# RadioGateway.net
KiCad netlist of a schematic drawn in EAGLE
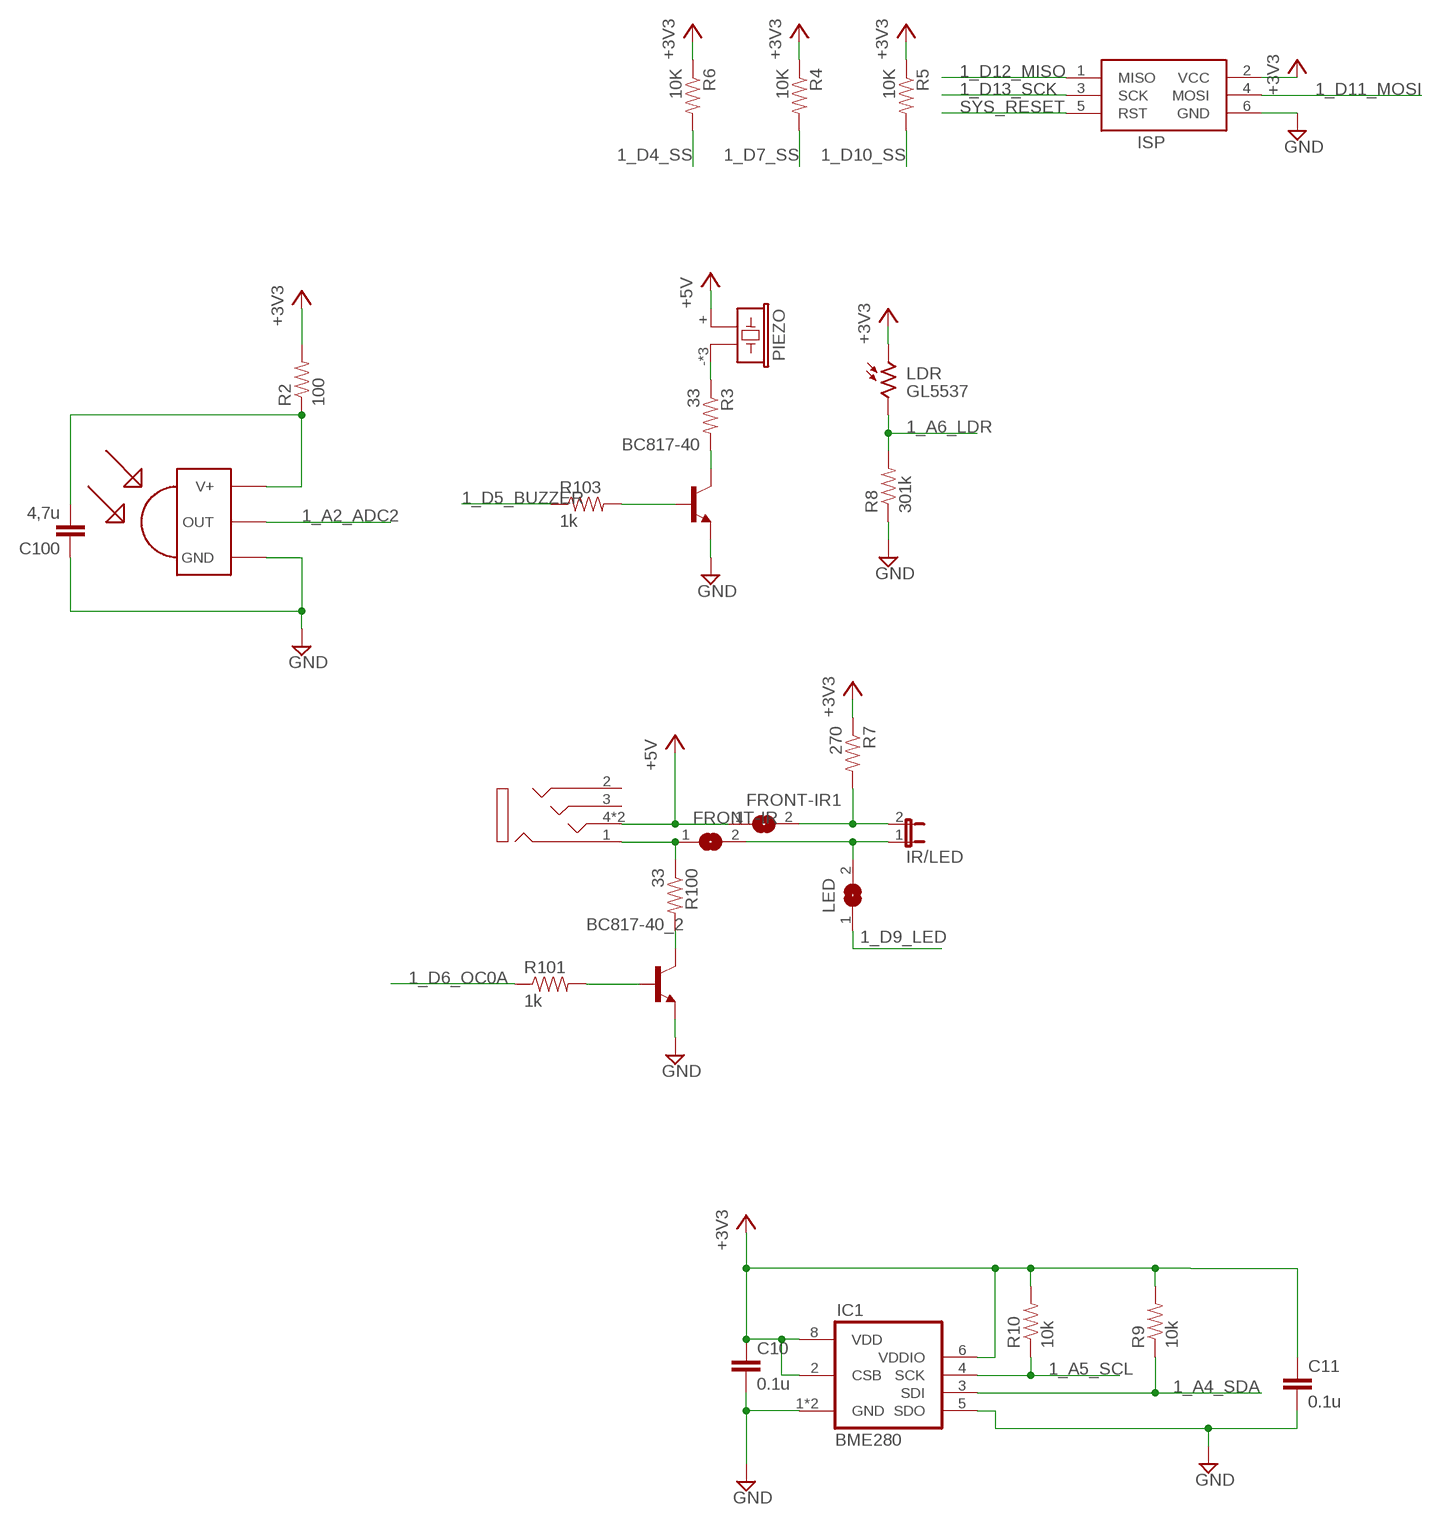
[diagram p0: schematic, sheet 1, part 1 of 2]
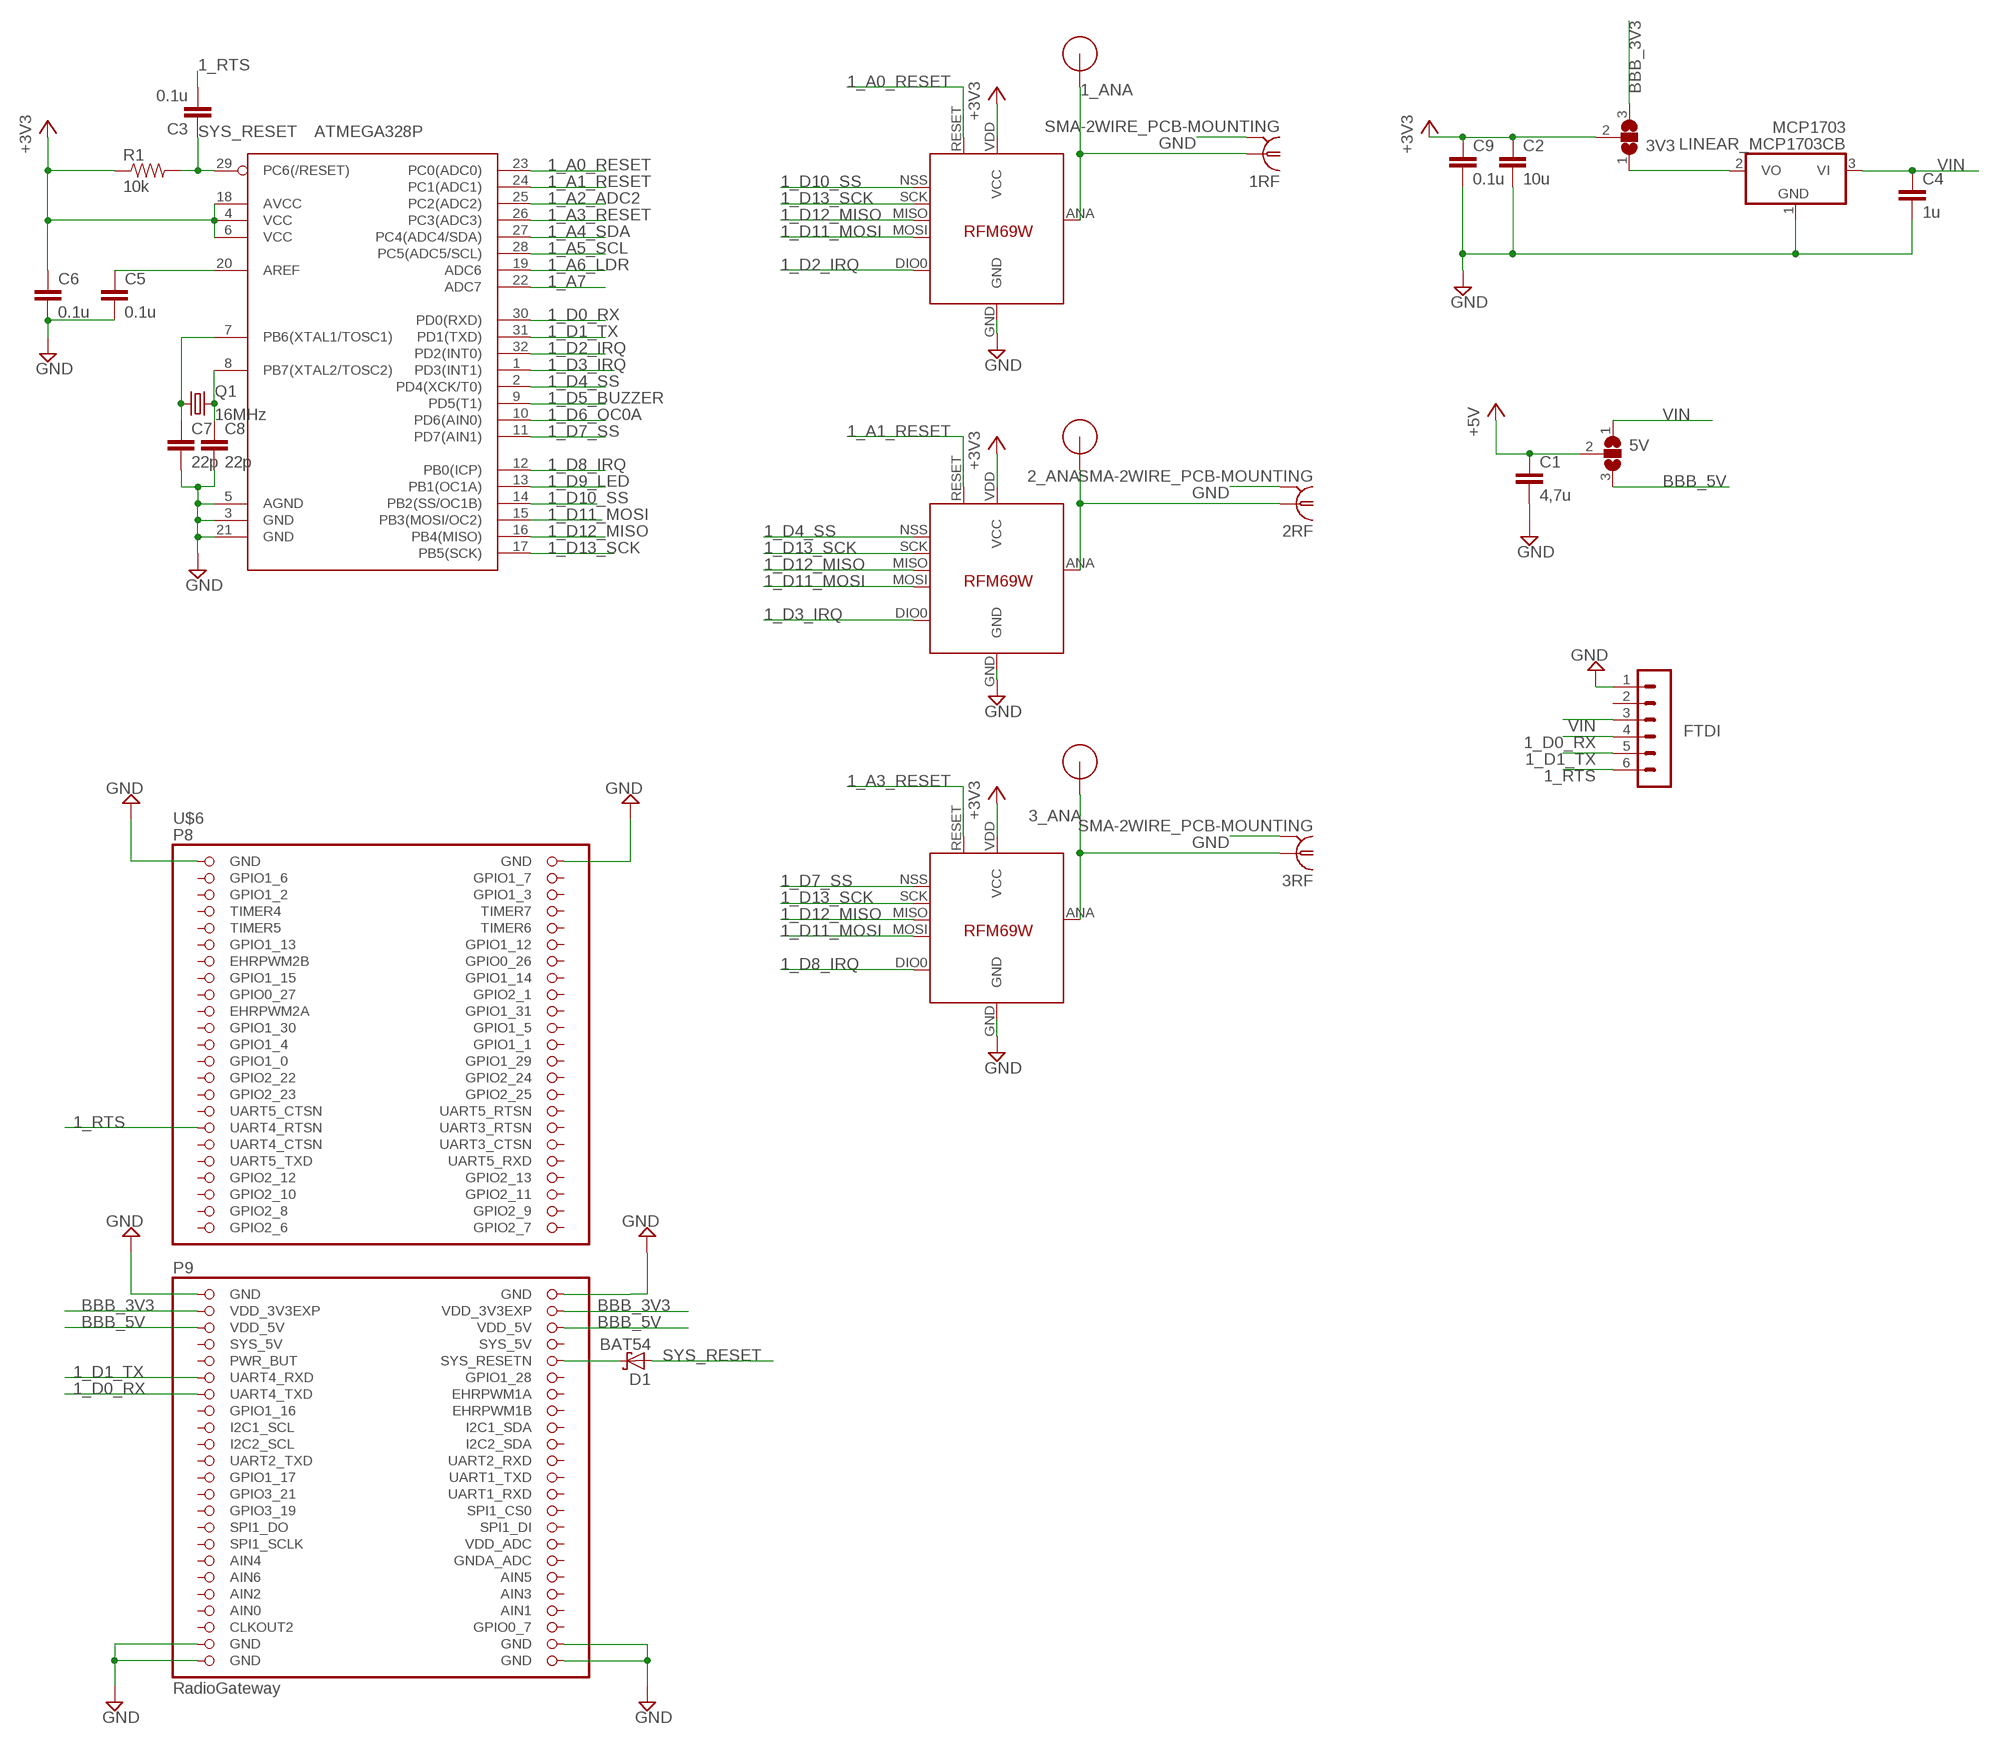
[diagram p1: schematic, sheet 1, part 2 of 2]

(export (version "E")
  (design (tool "Eeschema 10.0.6"))
  (components
    (comp (ref "1RF")
      (value "SMA-2WIRE_PCB-MOUNTING")
      (footprint "eagle-import:J01151A0931")
      (libsource (lib "eagle-import") (part "SMA-2WIRE_PCB-MOUNTING"))
    )
    (comp (ref "1_RFM69")
      (value "RFM69_MINIPADS")
      (footprint "eagle-import:RFM69W-MINPADS")
      (libsource (lib "eagle-import") (part "RFM69_MINIPADS"))
    )
    (comp (ref "2RF")
      (value "SMA-2WIRE_PCB-MOUNTING")
      (footprint "eagle-import:J01151A0931")
      (libsource (lib "eagle-import") (part "SMA-2WIRE_PCB-MOUNTING"))
    )
    (comp (ref "2_RFM69")
      (value "RFM69_MINIPADS")
      (footprint "eagle-import:RFM69W-MINPADS")
      (libsource (lib "eagle-import") (part "RFM69_MINIPADS"))
    )
    (comp (ref "3RF")
      (value "SMA-2WIRE_PCB-MOUNTING")
      (footprint "eagle-import:J01151A0931")
      (libsource (lib "eagle-import") (part "SMA-2WIRE_PCB-MOUNTING"))
    )
    (comp (ref "3V3")
      (value "SJ2W")
      (footprint "eagle-import:SJ_2")
      (libsource (lib "eagle-import") (part "SJ2W"))
    )
    (comp (ref "3_RFM69")
      (value "RFM69_MINIPADS")
      (footprint "eagle-import:RFM69W-MINPADS")
      (libsource (lib "eagle-import") (part "RFM69_MINIPADS"))
    )
    (comp (ref "5V")
      (value "SJ2W")
      (footprint "eagle-import:SJ_2")
      (libsource (lib "eagle-import") (part "SJ2W"))
    )
    (comp (ref "ATMEGA328P")
      (value "ATMega-328")
      (footprint "eagle-import:TQFP32-08")
      (libsource (lib "eagle-import") (part "ATMEGA168/328TQFP32"))
    )
    (comp (ref "BC817-40")
      (value "BC817-40-NPN-SOT23-BEC")
      (footprint "eagle-import:SOT23-BEC")
      (libsource (lib "eagle-import") (part "-NPN-SOT23-BECBC817-40"))
    )
    (comp (ref "BC817-40_2")
      (value "BC817-40-NPN-SOT23-BEC")
      (footprint "eagle-import:SOT23-BEC")
      (libsource (lib "eagle-import") (part "-NPN-SOT23-BECBC817-40"))
    )
    (comp (ref "C1")
      (value "4,7u")
      (footprint "eagle-import:0603-CAP")
      (libsource (lib "eagle-import") (part "CAP0603-CAP"))
    )
    (comp (ref "C2")
      (value "10u")
      (footprint "eagle-import:0603-CAP")
      (libsource (lib "eagle-import") (part "CAP0603-CAP"))
    )
    (comp (ref "C3")
      (value "0.1u")
      (footprint "eagle-import:0603-CAP")
      (libsource (lib "eagle-import") (part "CAP0603-CAP"))
    )
    (comp (ref "C4")
      (value "1u")
      (footprint "eagle-import:0603-CAP")
      (libsource (lib "eagle-import") (part "CAP0603-CAP"))
    )
    (comp (ref "C5")
      (value "0.1u")
      (footprint "eagle-import:0603-CAP")
      (libsource (lib "eagle-import") (part "CAP0603-CAP"))
    )
    (comp (ref "C6")
      (value "0.1u")
      (footprint "eagle-import:0603-CAP")
      (libsource (lib "eagle-import") (part "CAP0603-CAP"))
    )
    (comp (ref "C7")
      (value "22p")
      (footprint "eagle-import:0603-CAP")
      (libsource (lib "eagle-import") (part "CAP0603-CAP"))
    )
    (comp (ref "C8")
      (value "22p")
      (footprint "eagle-import:0603-CAP")
      (libsource (lib "eagle-import") (part "CAP0603-CAP"))
    )
    (comp (ref "C9")
      (value "0.1u")
      (footprint "eagle-import:0603-CAP")
      (libsource (lib "eagle-import") (part "CAP0603-CAP"))
    )
    (comp (ref "C10")
      (value "0.1u")
      (footprint "eagle-import:0603-CAP")
      (libsource (lib "eagle-import") (part "CAP0603-CAP"))
    )
    (comp (ref "C11")
      (value "0.1u")
      (footprint "eagle-import:0603-CAP")
      (libsource (lib "eagle-import") (part "CAP0603-CAP"))
    )
    (comp (ref "C100")
      (value "4,7u")
      (footprint "eagle-import:0603-CAP")
      (libsource (lib "eagle-import") (part "CAP0603-CAP"))
    )
    (comp (ref "D1")
      (value "BAT54")
      (footprint "eagle-import:SOT23")
      (libsource (lib "eagle-import") (part "BAT54"))
    )
    (comp (ref "FRONT-IR")
      (value "SJ")
      (footprint "eagle-import:SJ")
      (libsource (lib "eagle-import") (part "SJ"))
    )
    (comp (ref "FRONT-IR1")
      (value "SJ")
      (footprint "eagle-import:SJ")
      (libsource (lib "eagle-import") (part "SJ"))
    )
    (comp (ref "FTDI")
      (value "FTDI")
      (footprint "eagle-import:MA06-1")
      (libsource (lib "eagle-import") (part "MA06-1"))
    )
    (comp (ref "IC1")
      (value "BME280")
      (footprint "eagle-import:BME280")
      (libsource (lib "eagle-import") (part "BME280"))
    )
    (comp (ref "IR-RX")
      (value "TSOP4836")
      (footprint "eagle-import:TSOP18XX")
      (libsource (lib "eagle-import") (part "TSOP4836"))
    )
    (comp (ref "IR-TX")
      (value "1503_13")
      (footprint "eagle-import:1503-03")
      (libsource (lib "eagle-import") (part "1503_13"))
    )
    (comp (ref "IR/LED")
      (value "JP1E")
      (footprint "eagle-import:JP1")
      (libsource (lib "eagle-import") (part "JP1E"))
    )
    (comp (ref "ISP")
      (value "AVRISP-6")
      (footprint "eagle-import:AVRISP")
      (libsource (lib "eagle-import") (part "AVRISP-6"))
    )
    (comp (ref "LDR")
      (value "GL5537")
      (footprint "eagle-import:M9960")
      (libsource (lib "eagle-import") (part "M9960_11A"))
    )
    (comp (ref "LED") (value "SJ") (footprint "eagle-import:SJ") (libsource (lib "eagle-import") (part "SJ")))
    (comp (ref "MCP1703")
      (value "LINEAR_MCP1703CB")
      (footprint "eagle-import:LINEAR_SOT23")
      (libsource (lib "eagle-import") (part "LINEAR_MCP1703CB"))
    )
    (comp (ref "PIEZO")
      (value "BUZZER-PIEZO_SMD")
      (footprint "eagle-import:BUZZER-PIEZO_SMD")
      (libsource (lib "eagle-import") (part "BUZZER-PIEZO_SMD"))
    )
    (comp (ref "Q1")
      (value "16MHz")
      (footprint "eagle-import:HC49_S")
      (libsource (lib "eagle-import") (part "CRYSTALHC49S"))
    )
    (comp (ref "R1")
      (value "10k")
      (footprint "eagle-import:0603-RES")
      (libsource (lib "eagle-import") (part "RESISTOR0603-RES"))
    )
    (comp (ref "R2")
      (value "100")
      (footprint "eagle-import:0603-RES")
      (libsource (lib "eagle-import") (part "RESISTOR0603-RES"))
    )
    (comp (ref "R3")
      (value "33")
      (footprint "eagle-import:0603-RES")
      (libsource (lib "eagle-import") (part "RESISTOR0603-RES"))
    )
    (comp (ref "R4")
      (value "10K")
      (footprint "eagle-import:0603-RES")
      (libsource (lib "eagle-import") (part "RESISTOR0603-RES"))
    )
    (comp (ref "R5")
      (value "10K")
      (footprint "eagle-import:0603-RES")
      (libsource (lib "eagle-import") (part "RESISTOR0603-RES"))
    )
    (comp (ref "R6")
      (value "10K")
      (footprint "eagle-import:0603-RES")
      (libsource (lib "eagle-import") (part "RESISTOR0603-RES"))
    )
    (comp (ref "R7")
      (value "270")
      (footprint "eagle-import:0603-RES")
      (libsource (lib "eagle-import") (part "RESISTOR0603-RES"))
    )
    (comp (ref "R8")
      (value "301k")
      (footprint "eagle-import:0603-RES")
      (libsource (lib "eagle-import") (part "RESISTOR0603-RES"))
    )
    (comp (ref "R9")
      (value "10k")
      (footprint "eagle-import:0603-RES")
      (libsource (lib "eagle-import") (part "RESISTOR0603-RES"))
    )
    (comp (ref "R10")
      (value "10k")
      (footprint "eagle-import:0603-RES")
      (libsource (lib "eagle-import") (part "RESISTOR0603-RES"))
    )
    (comp (ref "R100")
      (value "33")
      (footprint "eagle-import:0603-RES")
      (libsource (lib "eagle-import") (part "RESISTOR0603-RES"))
    )
    (comp (ref "R101")
      (value "1k")
      (footprint "eagle-import:0603-RES")
      (libsource (lib "eagle-import") (part "RESISTOR0603-RES"))
    )
    (comp (ref "R103")
      (value "1k")
      (footprint "eagle-import:0603-RES")
      (libsource (lib "eagle-import") (part "RESISTOR0603-RES"))
    )
    (comp (ref "U$1")
      (value "RFM12B_ANTENNA")
      (footprint "eagle-import:RFM12B-ANTENNA")
      (libsource (lib "eagle-import") (part "RFM12B_ANTENNA"))
    )
    (comp (ref "U$2")
      (value "RFM12B_ANTENNA")
      (footprint "eagle-import:RFM12B-ANTENNA")
      (libsource (lib "eagle-import") (part "RFM12B_ANTENNA"))
    )
    (comp (ref "U$5")
      (value "RFM12B_ANTENNA")
      (footprint "eagle-import:RFM12B-ANTENNA")
      (libsource (lib "eagle-import") (part "RFM12B_ANTENNA"))
    )
    (comp (ref "U$6")
      (value "RadioGateway")
      (footprint "eagle-import:BEAGLEBONE_SHIELD")
      (libsource (lib "eagle-import") (part "BEAGLEBONE_OUTLINE"))
    )
  )
  (nets
    (net (code "1") (name "+3V3") (class "Default")
      (node (ref "1_RFM69") (pin "VDD") (pinfunction "VCC_VDD") (pintype "power_in"))
      (node (ref "2_RFM69") (pin "VDD") (pinfunction "VCC_VDD") (pintype "power_in"))
      (node (ref "3V3") (pin "2") (pinfunction "2_2") (pintype "passive"))
      (node (ref "3_RFM69") (pin "VDD") (pinfunction "VCC_VDD") (pintype "power_in"))
      (node (ref "ATMEGA328P") (pin "18") (pinfunction "AVCC_18") (pintype "bidirectional"))
      (node (ref "ATMEGA328P") (pin "4") (pinfunction "VCC_4") (pintype "bidirectional"))
      (node (ref "ATMEGA328P") (pin "6") (pinfunction "VCC_6") (pintype "bidirectional"))
      (node (ref "C10") (pin "1") (pinfunction "1_1") (pintype "passive"))
      (node (ref "C11") (pin "1") (pinfunction "1_1") (pintype "passive"))
      (node (ref "C2") (pin "1") (pinfunction "1_1") (pintype "passive"))
      (node (ref "C6") (pin "1") (pinfunction "1_1") (pintype "passive"))
      (node (ref "C9") (pin "1") (pinfunction "1_1") (pintype "passive"))
      (node (ref "IC1") (pin "2") (pinfunction "CSB_2") (pintype "input"))
      (node (ref "IC1") (pin "6") (pinfunction "VDDIO_6") (pintype "power_in"))
      (node (ref "IC1") (pin "8") (pinfunction "VDD_8") (pintype "power_in"))
      (node (ref "ISP") (pin "2") (pinfunction "VCC_2") (pintype "power_in"))
      (node (ref "LDR") (pin "1") (pinfunction "1_1") (pintype "passive"))
      (node (ref "R1") (pin "1") (pinfunction "1_1") (pintype "passive"))
      (node (ref "R10") (pin "2") (pinfunction "2_2") (pintype "passive"))
      (node (ref "R2") (pin "2") (pinfunction "2_2") (pintype "passive"))
      (node (ref "R4") (pin "1") (pinfunction "1_1") (pintype "passive"))
      (node (ref "R5") (pin "1") (pinfunction "1_1") (pintype "passive"))
      (node (ref "R6") (pin "1") (pinfunction "1_1") (pintype "passive"))
      (node (ref "R7") (pin "1") (pinfunction "1_1") (pintype "passive"))
      (node (ref "R9") (pin "2") (pinfunction "2_2") (pintype "passive"))
    )
    (net (code "2") (name "+5V") (class "Default")
      (node (ref "5V") (pin "2") (pinfunction "2_2") (pintype "passive"))
      (node (ref "C1") (pin "1") (pinfunction "1_1") (pintype "passive"))
      (node (ref "FRONT-IR1") (pin "1") (pinfunction "1_1") (pintype "passive"))
      (node (ref "IR-TX") (pin "4") (pinfunction "4_4") (pintype "bidirectional"))
      (node (ref "IR-TX") (pin "4-2") (pinfunction "4_4-2") (pintype "bidirectional"))
      (node (ref "PIEZO") (pin "+") (pinfunction "1_+") (pintype "passive"))
    )
    (net (code "3") (name "/1_A0_RESET") (class "Default")
      (node (ref "1_RFM69") (pin "RESET") (pinfunction "RESET_RESET") (pintype "input"))
      (node (ref "ATMEGA328P") (pin "23") (pinfunction "PC0(ADC0)_23") (pintype "bidirectional"))
    )
    (net (code "4") (name "/1_A1_RESET") (class "Default")
      (node (ref "2_RFM69") (pin "RESET") (pinfunction "RESET_RESET") (pintype "input"))
      (node (ref "ATMEGA328P") (pin "24") (pinfunction "PC1(ADC1)_24") (pintype "bidirectional"))
    )
    (net (code "5") (name "/1_A2_ADC2") (class "Default")
      (node (ref "ATMEGA328P") (pin "25") (pinfunction "PC2(ADC2)_25") (pintype "bidirectional"))
      (node (ref "IR-RX") (pin "OUT") (pinfunction "OUT_OUT") (pintype "bidirectional"))
    )
    (net (code "6") (name "/1_A3_RESET") (class "Default")
      (node (ref "3_RFM69") (pin "RESET") (pinfunction "RESET_RESET") (pintype "input"))
      (node (ref "ATMEGA328P") (pin "26") (pinfunction "PC3(ADC3)_26") (pintype "bidirectional"))
    )
    (net (code "7") (name "/1_A4_SDA") (class "Default")
      (node (ref "ATMEGA328P") (pin "27") (pinfunction "PC4(ADC4/SDA)_27") (pintype "bidirectional"))
      (node (ref "IC1") (pin "3") (pinfunction "SDI_3") (pintype "bidirectional"))
      (node (ref "R9") (pin "1") (pinfunction "1_1") (pintype "passive"))
    )
    (net (code "8") (name "/1_A5_SCL") (class "Default")
      (node (ref "ATMEGA328P") (pin "28") (pinfunction "PC5(ADC5/SCL)_28") (pintype "bidirectional"))
      (node (ref "IC1") (pin "4") (pinfunction "SCK_4") (pintype "bidirectional"))
      (node (ref "R10") (pin "1") (pinfunction "1_1") (pintype "passive"))
    )
    (net (code "9") (name "/1_A6_LDR") (class "Default")
      (node (ref "ATMEGA328P") (pin "19") (pinfunction "ADC6_19") (pintype "bidirectional"))
      (node (ref "LDR") (pin "2") (pinfunction "2_2") (pintype "passive"))
      (node (ref "R8") (pin "2") (pinfunction "2_2") (pintype "passive"))
    )
    (net (code "10") (name "/1_A7") (class "Default")
      (node (ref "ATMEGA328P") (pin "22") (pinfunction "ADC7_22") (pintype "bidirectional"))
    )
    (net (code "11") (name "/1_ANA") (class "Default")
      (node (ref "1RF") (pin "1") (pinfunction "1_1") (pintype "passive"))
      (node (ref "1_RFM69") (pin "ANA") (pinfunction "ANT_ANA") (pintype "passive"))
      (node (ref "U$1") (pin "P$1") (pinfunction "1_P$1") (pintype "bidirectional"))
    )
    (net (code "12") (name "/1_D0_RX") (class "Default")
      (node (ref "ATMEGA328P") (pin "30") (pinfunction "PD0(RXD)_30") (pintype "bidirectional"))
      (node (ref "FTDI") (pin "4") (pinfunction "4_4") (pintype "passive"))
      (node (ref "U$6") (pin "59") (pinfunction "UART4_TXD_59") (pintype "passive"))
    )
    (net (code "13") (name "/1_D1_TX") (class "Default")
      (node (ref "ATMEGA328P") (pin "31") (pinfunction "PD1(TXD)_31") (pintype "bidirectional"))
      (node (ref "FTDI") (pin "5") (pinfunction "5_5") (pintype "passive"))
      (node (ref "U$6") (pin "57") (pinfunction "UART4_RXD_57") (pintype "passive"))
    )
    (net (code "14") (name "/1_D2_IRQ") (class "Default")
      (node (ref "1_RFM69") (pin "DIO0") (pinfunction "DIO0/IRQ_DIO0") (pintype "open_collector"))
      (node (ref "ATMEGA328P") (pin "32") (pinfunction "PD2(INT0)_32") (pintype "bidirectional"))
    )
    (net (code "15") (name "/1_D3_IRQ") (class "Default")
      (node (ref "2_RFM69") (pin "DIO0") (pinfunction "DIO0/IRQ_DIO0") (pintype "open_collector"))
      (node (ref "ATMEGA328P") (pin "1") (pinfunction "PD3(INT1)_1") (pintype "bidirectional"))
    )
    (net (code "16") (name "/1_D4_SS") (class "Default")
      (node (ref "2_RFM69") (pin "NSS") (pinfunction "SEL_NSS") (pintype "input"))
      (node (ref "ATMEGA328P") (pin "2") (pinfunction "PD4(XCK/T0)_2") (pintype "bidirectional"))
      (node (ref "R6") (pin "2") (pinfunction "2_2") (pintype "passive"))
    )
    (net (code "17") (name "/1_D5_BUZZER") (class "Default")
      (node (ref "ATMEGA328P") (pin "9") (pinfunction "PD5(T1)_9") (pintype "bidirectional"))
      (node (ref "R103") (pin "1") (pinfunction "1_1") (pintype "passive"))
    )
    (net (code "18") (name "/1_D6_OC0A") (class "Default")
      (node (ref "ATMEGA328P") (pin "10") (pinfunction "PD6(AIN0)_10") (pintype "bidirectional"))
      (node (ref "R101") (pin "1") (pinfunction "1_1") (pintype "passive"))
    )
    (net (code "19") (name "/1_D7_SS") (class "Default")
      (node (ref "3_RFM69") (pin "NSS") (pinfunction "SEL_NSS") (pintype "input"))
      (node (ref "ATMEGA328P") (pin "11") (pinfunction "PD7(AIN1)_11") (pintype "bidirectional"))
      (node (ref "R4") (pin "2") (pinfunction "2_2") (pintype "passive"))
    )
    (net (code "20") (name "/1_D8_IRQ") (class "Default")
      (node (ref "3_RFM69") (pin "DIO0") (pinfunction "DIO0/IRQ_DIO0") (pintype "open_collector"))
      (node (ref "ATMEGA328P") (pin "12") (pinfunction "PB0(ICP)_12") (pintype "bidirectional"))
    )
    (net (code "21") (name "/1_D9_LED") (class "Default")
      (node (ref "ATMEGA328P") (pin "13") (pinfunction "PB1(OC1A)_13") (pintype "bidirectional"))
      (node (ref "LED") (pin "1") (pinfunction "1_1") (pintype "passive"))
    )
    (net (code "22") (name "/1_D10_SS") (class "Default")
      (node (ref "1_RFM69") (pin "NSS") (pinfunction "SEL_NSS") (pintype "input"))
      (node (ref "ATMEGA328P") (pin "14") (pinfunction "PB2(SS/OC1B)_14") (pintype "bidirectional"))
      (node (ref "R5") (pin "2") (pinfunction "2_2") (pintype "passive"))
    )
    (net (code "23") (name "/1_D11_MOSI") (class "Default")
      (node (ref "1_RFM69") (pin "MOSI") (pinfunction "MOSI_MOSI") (pintype "output"))
      (node (ref "2_RFM69") (pin "MOSI") (pinfunction "MOSI_MOSI") (pintype "output"))
      (node (ref "3_RFM69") (pin "MOSI") (pinfunction "MOSI_MOSI") (pintype "output"))
      (node (ref "ATMEGA328P") (pin "15") (pinfunction "PB3(MOSI/OC2)_15") (pintype "bidirectional"))
      (node (ref "ISP") (pin "4") (pinfunction "MOSI_4") (pintype "output"))
    )
    (net (code "24") (name "/1_D12_MISO") (class "Default")
      (node (ref "1_RFM69") (pin "MISO") (pinfunction "MISO_MISO") (pintype "input"))
      (node (ref "2_RFM69") (pin "MISO") (pinfunction "MISO_MISO") (pintype "input"))
      (node (ref "3_RFM69") (pin "MISO") (pinfunction "MISO_MISO") (pintype "input"))
      (node (ref "ATMEGA328P") (pin "16") (pinfunction "PB4(MISO)_16") (pintype "bidirectional"))
      (node (ref "ISP") (pin "1") (pinfunction "MISO_1") (pintype "input"))
    )
    (net (code "25") (name "/1_D13_SCK") (class "Default")
      (node (ref "1_RFM69") (pin "SCK") (pinfunction "SCK_SCK") (pintype "input"))
      (node (ref "2_RFM69") (pin "SCK") (pinfunction "SCK_SCK") (pintype "input"))
      (node (ref "3_RFM69") (pin "SCK") (pinfunction "SCK_SCK") (pintype "input"))
      (node (ref "ATMEGA328P") (pin "17") (pinfunction "PB5(SCK)_17") (pintype "bidirectional"))
      (node (ref "ISP") (pin "3") (pinfunction "SCK_3") (pintype "output"))
    )
    (net (code "26") (name "/1_RTS") (class "Default")
      (node (ref "C3") (pin "2") (pinfunction "2_2") (pintype "passive"))
      (node (ref "FTDI") (pin "6") (pinfunction "6_6") (pintype "passive"))
      (node (ref "U$6") (pin "33") (pinfunction "UART4_RTSN_33") (pintype "passive"))
    )
    (net (code "27") (name "/2_ANA") (class "Default")
      (node (ref "2RF") (pin "1") (pinfunction "1_1") (pintype "passive"))
      (node (ref "2_RFM69") (pin "ANA") (pinfunction "ANT_ANA") (pintype "passive"))
      (node (ref "U$5") (pin "P$1") (pinfunction "1_P$1") (pintype "bidirectional"))
    )
    (net (code "28") (name "/3_ANA") (class "Default")
      (node (ref "3RF") (pin "1") (pinfunction "1_1") (pintype "passive"))
      (node (ref "3_RFM69") (pin "ANA") (pinfunction "ANT_ANA") (pintype "passive"))
      (node (ref "U$2") (pin "P$1") (pinfunction "1_P$1") (pintype "bidirectional"))
    )
    (net (code "29") (name "/AIN0") (class "Default")
      (node (ref "U$6") (pin "85") (pinfunction "AIN0_85") (pintype "power_in"))
    )
    (net (code "30") (name "/BBB_3V3") (class "Default")
      (node (ref "3V3") (pin "3") (pinfunction "3_3") (pintype "passive"))
      (node (ref "U$6") (pin "49") (pinfunction "VDD_3V3EXP_49") (pintype "power_in"))
      (node (ref "U$6") (pin "50") (pinfunction "VDD_3V3EXP_50") (pintype "power_in"))
    )
    (net (code "31") (name "/BBB_5V") (class "Default")
      (node (ref "5V") (pin "3") (pinfunction "3_3") (pintype "passive"))
      (node (ref "U$6") (pin "51") (pinfunction "VDD_5V_51") (pintype "power_in"))
      (node (ref "U$6") (pin "52") (pinfunction "VDD_5V_52") (pintype "power_in"))
    )
    (net (code "32") (name "/SYS_5V") (class "Default")
      (node (ref "U$6") (pin "53") (pinfunction "SYS_5V_53") (pintype "power_in"))
    )
    (net (code "33") (name "/SYS_RESET") (class "Default")
      (node (ref "ATMEGA328P") (pin "29") (pinfunction "PC6(/RESET)_29") (pintype "bidirectional"))
      (node (ref "C3") (pin "1") (pinfunction "1_1") (pintype "passive"))
      (node (ref "D1") (pin "1") (pinfunction "A_1") (pintype "passive"))
      (node (ref "ISP") (pin "5") (pinfunction "RST_5") (pintype "output"))
      (node (ref "R1") (pin "2") (pinfunction "2_2") (pintype "passive"))
    )
    (net (code "34") (name "/VIN") (class "Default")
      (node (ref "5V") (pin "1") (pinfunction "1_1") (pintype "passive"))
      (node (ref "C4") (pin "1") (pinfunction "1_1") (pintype "passive"))
      (node (ref "FTDI") (pin "3") (pinfunction "3_3") (pintype "passive"))
      (node (ref "MCP1703") (pin "3") (pinfunction "VI_3") (pintype "input"))
    )
    (net (code "35") (name "GND") (class "Default")
      (node (ref "1RF") (pin "G@1") (pinfunction "2_G@1") (pintype "passive"))
      (node (ref "1RF") (pin "G@2") (pinfunction "2_G@2") (pintype "passive"))
      (node (ref "1RF") (pin "G@3") (pinfunction "2_G@3") (pintype "passive"))
      (node (ref "1RF") (pin "G@4") (pinfunction "2_G@4") (pintype "passive"))
      (node (ref "1_RFM69") (pin "GND") (pinfunction "GND_GND") (pintype "power_in"))
      (node (ref "2RF") (pin "G@1") (pinfunction "2_G@1") (pintype "passive"))
      (node (ref "2RF") (pin "G@2") (pinfunction "2_G@2") (pintype "passive"))
      (node (ref "2RF") (pin "G@3") (pinfunction "2_G@3") (pintype "passive"))
      (node (ref "2RF") (pin "G@4") (pinfunction "2_G@4") (pintype "passive"))
      (node (ref "2_RFM69") (pin "GND") (pinfunction "GND_GND") (pintype "power_in"))
      (node (ref "3RF") (pin "G@1") (pinfunction "2_G@1") (pintype "passive"))
      (node (ref "3RF") (pin "G@2") (pinfunction "2_G@2") (pintype "passive"))
      (node (ref "3RF") (pin "G@3") (pinfunction "2_G@3") (pintype "passive"))
      (node (ref "3RF") (pin "G@4") (pinfunction "2_G@4") (pintype "passive"))
      (node (ref "3_RFM69") (pin "GND") (pinfunction "GND_GND") (pintype "power_in"))
      (node (ref "ATMEGA328P") (pin "21") (pinfunction "GND_21") (pintype "bidirectional"))
      (node (ref "ATMEGA328P") (pin "3") (pinfunction "GND_3") (pintype "bidirectional"))
      (node (ref "ATMEGA328P") (pin "5") (pinfunction "AGND_5") (pintype "bidirectional"))
      (node (ref "BC817-40") (pin "E") (pinfunction "E_E") (pintype "passive"))
      (node (ref "BC817-40_2") (pin "E") (pinfunction "E_E") (pintype "passive"))
      (node (ref "C1") (pin "2") (pinfunction "2_2") (pintype "passive"))
      (node (ref "C10") (pin "2") (pinfunction "2_2") (pintype "passive"))
      (node (ref "C100") (pin "1") (pinfunction "1_1") (pintype "passive"))
      (node (ref "C11") (pin "2") (pinfunction "2_2") (pintype "passive"))
      (node (ref "C2") (pin "2") (pinfunction "2_2") (pintype "passive"))
      (node (ref "C4") (pin "2") (pinfunction "2_2") (pintype "passive"))
      (node (ref "C5") (pin "2") (pinfunction "2_2") (pintype "passive"))
      (node (ref "C6") (pin "2") (pinfunction "2_2") (pintype "passive"))
      (node (ref "C7") (pin "2") (pinfunction "2_2") (pintype "passive"))
      (node (ref "C8") (pin "2") (pinfunction "2_2") (pintype "passive"))
      (node (ref "C9") (pin "2") (pinfunction "2_2") (pintype "passive"))
      (node (ref "FTDI") (pin "1") (pinfunction "1_1") (pintype "passive"))
      (node (ref "IC1") (pin "1") (pinfunction "GND_1") (pintype "power_in"))
      (node (ref "IC1") (pin "5") (pinfunction "SDO_5") (pintype "input"))
      (node (ref "IC1") (pin "7") (pinfunction "GND_7") (pintype "power_in"))
      (node (ref "IR-RX") (pin "GND") (pinfunction "GND_GND") (pintype "bidirectional"))
      (node (ref "ISP") (pin "6") (pinfunction "GND_6") (pintype "power_in"))
      (node (ref "MCP1703") (pin "1") (pinfunction "GND_1") (pintype "passive"))
      (node (ref "R8") (pin "1") (pinfunction "1_1") (pintype "passive"))
      (node (ref "U$6") (pin "1") (pinfunction "GND_1") (pintype "power_in"))
      (node (ref "U$6") (pin "2") (pinfunction "GND_2") (pintype "power_in"))
      (node (ref "U$6") (pin "47") (pinfunction "GND_47") (pintype "power_in"))
      (node (ref "U$6") (pin "48") (pinfunction "GND_48") (pintype "power_in"))
      (node (ref "U$6") (pin "89") (pinfunction "GND_89") (pintype "power_in"))
      (node (ref "U$6") (pin "90") (pinfunction "GND_90") (pintype "power_in"))
      (node (ref "U$6") (pin "91") (pinfunction "GND_91") (pintype "power_in"))
      (node (ref "U$6") (pin "92") (pinfunction "GND_92") (pintype "power_in"))
    )
    (net (code "36") (name "Net-(ATMEGA328P-AREF)") (class "Default")
      (node (ref "ATMEGA328P") (pin "20") (pinfunction "AREF_20") (pintype "bidirectional"))
      (node (ref "C5") (pin "1") (pinfunction "1_1") (pintype "passive"))
    )
    (net (code "37") (name "Net-(ATMEGA328P-PB6(XTAL1{slash}TOSC1))") (class "Default")
      (node (ref "ATMEGA328P") (pin "7") (pinfunction "PB6(XTAL1/TOSC1)_7") (pintype "bidirectional"))
      (node (ref "C7") (pin "1") (pinfunction "1_1") (pintype "passive"))
      (node (ref "Q1") (pin "1") (pinfunction "1_1") (pintype "passive"))
    )
    (net (code "38") (name "Net-(ATMEGA328P-PB7(XTAL2{slash}TOSC2))") (class "Default")
      (node (ref "ATMEGA328P") (pin "8") (pinfunction "PB7(XTAL2/TOSC2)_8") (pintype "bidirectional"))
      (node (ref "C8") (pin "1") (pinfunction "1_1") (pintype "passive"))
      (node (ref "Q1") (pin "2") (pinfunction "2_2") (pintype "passive"))
    )
    (net (code "39") (name "Net-(BC817-40-PadB)") (class "Default")
      (node (ref "BC817-40") (pin "B") (pinfunction "B_B") (pintype "passive"))
      (node (ref "R103") (pin "2") (pinfunction "2_2") (pintype "passive"))
    )
    (net (code "40") (name "Net-(BC817-40-PadC)") (class "Default")
      (node (ref "BC817-40") (pin "C") (pinfunction "C_C") (pintype "passive"))
      (node (ref "R3") (pin "2") (pinfunction "2_2") (pintype "passive"))
    )
    (net (code "41") (name "Net-(BC817-40_2-PadB)") (class "Default")
      (node (ref "BC817-40_2") (pin "B") (pinfunction "B_B") (pintype "passive"))
      (node (ref "R101") (pin "2") (pinfunction "2_2") (pintype "passive"))
    )
    (net (code "42") (name "Net-(BC817-40_2-PadC)") (class "Default")
      (node (ref "BC817-40_2") (pin "C") (pinfunction "C_C") (pintype "passive"))
      (node (ref "R100") (pin "2") (pinfunction "2_2") (pintype "passive"))
    )
    (net (code "43") (name "Net-(D1-C)") (class "Default")
      (node (ref "D1") (pin "3") (pinfunction "C_3") (pintype "passive"))
      (node (ref "U$6") (pin "56") (pinfunction "SYS_RESETN_56") (pintype "passive"))
    )
    (net (code "44") (name "Net-(FRONT-IR-Pad1)") (class "Default")
      (node (ref "FRONT-IR") (pin "1") (pinfunction "1_1") (pintype "passive"))
      (node (ref "IR-TX") (pin "1") (pinfunction "1_1") (pintype "bidirectional"))
      (node (ref "R100") (pin "1") (pinfunction "1_1") (pintype "passive"))
    )
    (net (code "45") (name "Net-(FRONT-IR-Pad2)") (class "Default")
      (node (ref "FRONT-IR") (pin "2") (pinfunction "2_2") (pintype "passive"))
      (node (ref "IR/LED") (pin "1") (pinfunction "1_1") (pintype "passive"))
      (node (ref "LED") (pin "2") (pinfunction "2_2") (pintype "passive"))
    )
    (net (code "46") (name "Net-(FRONT-IR1-Pad2)") (class "Default")
      (node (ref "FRONT-IR1") (pin "2") (pinfunction "2_2") (pintype "passive"))
      (node (ref "IR/LED") (pin "2") (pinfunction "2_2") (pintype "passive"))
      (node (ref "R7") (pin "2") (pinfunction "2_2") (pintype "passive"))
    )
    (net (code "47") (name "Net-(IR-RX-V+)") (class "Default")
      (node (ref "C100") (pin "2") (pinfunction "2_2") (pintype "passive"))
      (node (ref "IR-RX") (pin "VCC") (pinfunction "V+_VCC") (pintype "bidirectional"))
      (node (ref "R2") (pin "1") (pinfunction "1_1") (pintype "passive"))
    )
    (net (code "48") (name "Net-(MCP1703-VO)") (class "Default")
      (node (ref "3V3") (pin "1") (pinfunction "1_1") (pintype "passive"))
      (node (ref "MCP1703") (pin "2") (pinfunction "VO_2") (pintype "passive"))
    )
    (net (code "49") (name "Net-(PIEZO-2-Pad-)") (class "Default")
      (node (ref "PIEZO") (pin "-") (pinfunction "2_-") (pintype "passive"))
      (node (ref "PIEZO") (pin "DUMMY") (pinfunction "2_DUMMY") (pintype "passive"))
      (node (ref "PIEZO") (pin "DUMMY1") (pinfunction "2_DUMMY1") (pintype "passive"))
      (node (ref "R3") (pin "1") (pinfunction "1_1") (pintype "passive"))
    )
    (net (code "50") (name "unconnected-(FTDI-Pad2)") (class "Default")
      (node (ref "FTDI") (pin "2") (pinfunction "2_2") (pintype "passive"))
    )
    (net (code "51") (name "unconnected-(IR-TX-Pad2)") (class "Default")
      (node (ref "IR-TX") (pin "2") (pinfunction "2_2") (pintype "bidirectional"))
    )
    (net (code "52") (name "unconnected-(IR-TX-Pad3)") (class "Default")
      (node (ref "IR-TX") (pin "3") (pinfunction "3_3") (pintype "bidirectional"))
    )
    (net (code "53") (name "unconnected-(U$6-AIN1-Pad86)") (class "Default")
      (node (ref "U$6") (pin "86") (pinfunction "AIN1_86") (pintype "passive"))
    )
    (net (code "54") (name "unconnected-(U$6-AIN2-Pad83)") (class "Default")
      (node (ref "U$6") (pin "83") (pinfunction "AIN2_83") (pintype "passive"))
    )
    (net (code "55") (name "unconnected-(U$6-AIN3-Pad84)") (class "Default")
      (node (ref "U$6") (pin "84") (pinfunction "AIN3_84") (pintype "passive"))
    )
    (net (code "56") (name "unconnected-(U$6-AIN4-Pad79)") (class "Default")
      (node (ref "U$6") (pin "79") (pinfunction "AIN4_79") (pintype "passive"))
    )
    (net (code "57") (name "unconnected-(U$6-AIN5-Pad82)") (class "Default")
      (node (ref "U$6") (pin "82") (pinfunction "AIN5_82") (pintype "passive"))
    )
    (net (code "58") (name "unconnected-(U$6-AIN6-Pad81)") (class "Default")
      (node (ref "U$6") (pin "81") (pinfunction "AIN6_81") (pintype "passive"))
    )
    (net (code "59") (name "unconnected-(U$6-CLKOUT2-Pad87)") (class "Default")
      (node (ref "U$6") (pin "87") (pinfunction "CLKOUT2_87") (pintype "input"))
    )
    (net (code "60") (name "unconnected-(U$6-EHRPWM1A-Pad60)") (class "Default")
      (node (ref "U$6") (pin "60") (pinfunction "EHRPWM1A_60") (pintype "passive"))
    )
    (net (code "61") (name "unconnected-(U$6-EHRPWM1B-Pad62)") (class "Default")
      (node (ref "U$6") (pin "62") (pinfunction "EHRPWM1B_62") (pintype "passive"))
    )
    (net (code "62") (name "unconnected-(U$6-EHRPWM2A-Pad19)") (class "Default")
      (node (ref "U$6") (pin "19") (pinfunction "EHRPWM2A_19") (pintype "passive"))
    )
    (net (code "63") (name "unconnected-(U$6-EHRPWM2B-Pad13)") (class "Default")
      (node (ref "U$6") (pin "13") (pinfunction "EHRPWM2B_13") (pintype "passive"))
    )
    (net (code "64") (name "unconnected-(U$6-GNDA_ADC-Pad80)") (class "Default")
      (node (ref "U$6") (pin "80") (pinfunction "GNDA_ADC_80") (pintype "passive"))
    )
    (net (code "65") (name "unconnected-(U$6-GPIO0_7-Pad88)") (class "Default")
      (node (ref "U$6") (pin "88") (pinfunction "GPIO0_7_88") (pintype "passive"))
    )
    (net (code "66") (name "unconnected-(U$6-GPIO0_26-Pad14)") (class "Default")
      (node (ref "U$6") (pin "14") (pinfunction "GPIO0_26_14") (pintype "passive"))
    )
    (net (code "67") (name "unconnected-(U$6-GPIO0_27-Pad17)") (class "Default")
      (node (ref "U$6") (pin "17") (pinfunction "GPIO0_27_17") (pintype "passive"))
    )
    (net (code "68") (name "unconnected-(U$6-GPIO1_0-Pad25)") (class "Default")
      (node (ref "U$6") (pin "25") (pinfunction "GPIO1_0_25") (pintype "passive"))
    )
    (net (code "69") (name "unconnected-(U$6-GPIO1_1-Pad24)") (class "Default")
      (node (ref "U$6") (pin "24") (pinfunction "GPIO1_1_24") (pintype "passive"))
    )
    (net (code "70") (name "unconnected-(U$6-GPIO1_2-Pad5)") (class "Default")
      (node (ref "U$6") (pin "5") (pinfunction "GPIO1_2_5") (pintype "passive"))
    )
    (net (code "71") (name "unconnected-(U$6-GPIO1_3-Pad6)") (class "Default")
      (node (ref "U$6") (pin "6") (pinfunction "GPIO1_3_6") (pintype "passive"))
    )
    (net (code "72") (name "unconnected-(U$6-GPIO1_4-Pad23)") (class "Default")
      (node (ref "U$6") (pin "23") (pinfunction "GPIO1_4_23") (pintype "passive"))
    )
    (net (code "73") (name "unconnected-(U$6-GPIO1_5-Pad22)") (class "Default")
      (node (ref "U$6") (pin "22") (pinfunction "GPIO1_5_22") (pintype "passive"))
    )
    (net (code "74") (name "unconnected-(U$6-GPIO1_6-Pad3)") (class "Default")
      (node (ref "U$6") (pin "3") (pinfunction "GPIO1_6_3") (pintype "passive"))
    )
    (net (code "75") (name "unconnected-(U$6-GPIO1_7-Pad4)") (class "Default")
      (node (ref "U$6") (pin "4") (pinfunction "GPIO1_7_4") (pintype "passive"))
    )
    (net (code "76") (name "unconnected-(U$6-GPIO1_12-Pad12)") (class "Default")
      (node (ref "U$6") (pin "12") (pinfunction "GPIO1_12_12") (pintype "passive"))
    )
    (net (code "77") (name "unconnected-(U$6-GPIO1_13-Pad11)") (class "Default")
      (node (ref "U$6") (pin "11") (pinfunction "GPIO1_13_11") (pintype "passive"))
    )
    (net (code "78") (name "unconnected-(U$6-GPIO1_14-Pad16)") (class "Default")
      (node (ref "U$6") (pin "16") (pinfunction "GPIO1_14_16") (pintype "passive"))
    )
    (net (code "79") (name "unconnected-(U$6-GPIO1_15-Pad15)") (class "Default")
      (node (ref "U$6") (pin "15") (pinfunction "GPIO1_15_15") (pintype "passive"))
    )
    (net (code "80") (name "unconnected-(U$6-GPIO1_16-Pad61)") (class "Default")
      (node (ref "U$6") (pin "61") (pinfunction "GPIO1_16_61") (pintype "passive"))
    )
    (net (code "81") (name "unconnected-(U$6-GPIO1_17-Pad69)") (class "Default")
      (node (ref "U$6") (pin "69") (pinfunction "GPIO1_17_69") (pintype "passive"))
    )
    (net (code "82") (name "unconnected-(U$6-GPIO1_28-Pad58)") (class "Default")
      (node (ref "U$6") (pin "58") (pinfunction "GPIO1_28_58") (pintype "passive"))
    )
    (net (code "83") (name "unconnected-(U$6-GPIO1_29-Pad26)") (class "Default")
      (node (ref "U$6") (pin "26") (pinfunction "GPIO1_29_26") (pintype "passive"))
    )
    (net (code "84") (name "unconnected-(U$6-GPIO1_30-Pad21)") (class "Default")
      (node (ref "U$6") (pin "21") (pinfunction "GPIO1_30_21") (pintype "passive"))
    )
    (net (code "85") (name "unconnected-(U$6-GPIO1_31-Pad20)") (class "Default")
      (node (ref "U$6") (pin "20") (pinfunction "GPIO1_31_20") (pintype "passive"))
    )
    (net (code "86") (name "unconnected-(U$6-GPIO2_1-Pad18)") (class "Default")
      (node (ref "U$6") (pin "18") (pinfunction "GPIO2_1_18") (pintype "passive"))
    )
    (net (code "87") (name "unconnected-(U$6-GPIO2_6-Pad45)") (class "Default")
      (node (ref "U$6") (pin "45") (pinfunction "GPIO2_6_45") (pintype "passive"))
    )
    (net (code "88") (name "unconnected-(U$6-GPIO2_7-Pad46)") (class "Default")
      (node (ref "U$6") (pin "46") (pinfunction "GPIO2_7_46") (pintype "passive"))
    )
    (net (code "89") (name "unconnected-(U$6-GPIO2_8-Pad43)") (class "Default")
      (node (ref "U$6") (pin "43") (pinfunction "GPIO2_8_43") (pintype "passive"))
    )
    (net (code "90") (name "unconnected-(U$6-GPIO2_9-Pad44)") (class "Default")
      (node (ref "U$6") (pin "44") (pinfunction "GPIO2_9_44") (pintype "passive"))
    )
    (net (code "91") (name "unconnected-(U$6-GPIO2_10-Pad41)") (class "Default")
      (node (ref "U$6") (pin "41") (pinfunction "GPIO2_10_41") (pintype "passive"))
    )
    (net (code "92") (name "unconnected-(U$6-GPIO2_11-Pad42)") (class "Default")
      (node (ref "U$6") (pin "42") (pinfunction "GPIO2_11_42") (pintype "passive"))
    )
    (net (code "93") (name "unconnected-(U$6-GPIO2_12-Pad39)") (class "Default")
      (node (ref "U$6") (pin "39") (pinfunction "GPIO2_12_39") (pintype "passive"))
    )
    (net (code "94") (name "unconnected-(U$6-GPIO2_13-Pad40)") (class "Default")
      (node (ref "U$6") (pin "40") (pinfunction "GPIO2_13_40") (pintype "passive"))
    )
    (net (code "95") (name "unconnected-(U$6-GPIO2_22-Pad27)") (class "Default")
      (node (ref "U$6") (pin "27") (pinfunction "GPIO2_22_27") (pintype "passive"))
    )
    (net (code "96") (name "unconnected-(U$6-GPIO2_23-Pad29)") (class "Default")
      (node (ref "U$6") (pin "29") (pinfunction "GPIO2_23_29") (pintype "passive"))
    )
    (net (code "97") (name "unconnected-(U$6-GPIO2_24-Pad28)") (class "Default")
      (node (ref "U$6") (pin "28") (pinfunction "GPIO2_24_28") (pintype "passive"))
    )
    (net (code "98") (name "unconnected-(U$6-GPIO2_25-Pad30)") (class "Default")
      (node (ref "U$6") (pin "30") (pinfunction "GPIO2_25_30") (pintype "passive"))
    )
    (net (code "99") (name "unconnected-(U$6-GPIO3_19-Pad73)") (class "Default")
      (node (ref "U$6") (pin "73") (pinfunction "GPIO3_19_73") (pintype "passive"))
    )
    (net (code "100") (name "unconnected-(U$6-GPIO3_21-Pad71)") (class "Default")
      (node (ref "U$6") (pin "71") (pinfunction "GPIO3_21_71") (pintype "passive"))
    )
    (net (code "101") (name "unconnected-(U$6-I2C1_SCL-Pad63)") (class "Default")
      (node (ref "U$6") (pin "63") (pinfunction "I2C1_SCL_63") (pintype "passive"))
    )
    (net (code "102") (name "unconnected-(U$6-I2C1_SDA-Pad64)") (class "Default")
      (node (ref "U$6") (pin "64") (pinfunction "I2C1_SDA_64") (pintype "passive"))
    )
    (net (code "103") (name "unconnected-(U$6-I2C2_SCL-Pad65)") (class "Default")
      (node (ref "U$6") (pin "65") (pinfunction "I2C2_SCL_65") (pintype "passive"))
    )
    (net (code "104") (name "unconnected-(U$6-I2C2_SDA-Pad66)") (class "Default")
      (node (ref "U$6") (pin "66") (pinfunction "I2C2_SDA_66") (pintype "passive"))
    )
    (net (code "105") (name "unconnected-(U$6-PWR_BUT-Pad55)") (class "Default")
      (node (ref "U$6") (pin "55") (pinfunction "PWR_BUT_55") (pintype "passive"))
    )
    (net (code "106") (name "unconnected-(U$6-SPI1_CS0-Pad74)") (class "Default")
      (node (ref "U$6") (pin "74") (pinfunction "SPI1_CS0_74") (pintype "passive"))
    )
    (net (code "107") (name "unconnected-(U$6-SPI1_DI-Pad76)") (class "Default")
      (node (ref "U$6") (pin "76") (pinfunction "SPI1_DI_76") (pintype "passive"))
    )
    (net (code "108") (name "unconnected-(U$6-SPI1_DO-Pad75)") (class "Default")
      (node (ref "U$6") (pin "75") (pinfunction "SPI1_DO_75") (pintype "passive"))
    )
    (net (code "109") (name "unconnected-(U$6-SPI1_SCLK-Pad77)") (class "Default")
      (node (ref "U$6") (pin "77") (pinfunction "SPI1_SCLK_77") (pintype "passive"))
    )
    (net (code "110") (name "unconnected-(U$6-SYS_5V-Pad54)") (class "Default")
      (node (ref "U$6") (pin "54") (pinfunction "SYS_5V_54") (pintype "passive"))
    )
    (net (code "111") (name "unconnected-(U$6-TIMER4-Pad7)") (class "Default")
      (node (ref "U$6") (pin "7") (pinfunction "TIMER4_7") (pintype "passive"))
    )
    (net (code "112") (name "unconnected-(U$6-TIMER5-Pad9)") (class "Default")
      (node (ref "U$6") (pin "9") (pinfunction "TIMER5_9") (pintype "passive"))
    )
    (net (code "113") (name "unconnected-(U$6-TIMER6-Pad10)") (class "Default")
      (node (ref "U$6") (pin "10") (pinfunction "TIMER6_10") (pintype "passive"))
    )
    (net (code "114") (name "unconnected-(U$6-TIMER7-Pad8)") (class "Default")
      (node (ref "U$6") (pin "8") (pinfunction "TIMER7_8") (pintype "passive"))
    )
    (net (code "115") (name "unconnected-(U$6-UART1_RXD-Pad72)") (class "Default")
      (node (ref "U$6") (pin "72") (pinfunction "UART1_RXD_72") (pintype "passive"))
    )
    (net (code "116") (name "unconnected-(U$6-UART1_TXD-Pad70)") (class "Default")
      (node (ref "U$6") (pin "70") (pinfunction "UART1_TXD_70") (pintype "passive"))
    )
    (net (code "117") (name "unconnected-(U$6-UART2_RXD-Pad68)") (class "Default")
      (node (ref "U$6") (pin "68") (pinfunction "UART2_RXD_68") (pintype "passive"))
    )
    (net (code "118") (name "unconnected-(U$6-UART2_TXD-Pad67)") (class "Default")
      (node (ref "U$6") (pin "67") (pinfunction "UART2_TXD_67") (pintype "passive"))
    )
    (net (code "119") (name "unconnected-(U$6-UART3_CTSN-Pad36)") (class "Default")
      (node (ref "U$6") (pin "36") (pinfunction "UART3_CTSN_36") (pintype "passive"))
    )
    (net (code "120") (name "unconnected-(U$6-UART3_RTSN-Pad34)") (class "Default")
      (node (ref "U$6") (pin "34") (pinfunction "UART3_RTSN_34") (pintype "passive"))
    )
    (net (code "121") (name "unconnected-(U$6-UART4_CTSN-Pad35)") (class "Default")
      (node (ref "U$6") (pin "35") (pinfunction "UART4_CTSN_35") (pintype "passive"))
    )
    (net (code "122") (name "unconnected-(U$6-UART5_CTSN-Pad31)") (class "Default")
      (node (ref "U$6") (pin "31") (pinfunction "UART5_CTSN_31") (pintype "passive"))
    )
    (net (code "123") (name "unconnected-(U$6-UART5_RTSN-Pad32)") (class "Default")
      (node (ref "U$6") (pin "32") (pinfunction "UART5_RTSN_32") (pintype "passive"))
    )
    (net (code "124") (name "unconnected-(U$6-UART5_RXD-Pad38)") (class "Default")
      (node (ref "U$6") (pin "38") (pinfunction "UART5_RXD_38") (pintype "passive"))
    )
    (net (code "125") (name "unconnected-(U$6-UART5_TXD-Pad37)") (class "Default")
      (node (ref "U$6") (pin "37") (pinfunction "UART5_TXD_37") (pintype "passive"))
    )
    (net (code "126") (name "unconnected-(U$6-VDD_ADC-Pad78)") (class "Default")
      (node (ref "U$6") (pin "78") (pinfunction "VDD_ADC_78") (pintype "passive"))
    )
  )
)
